# Box-3_Electronics_v6.net
KiCad netlist of a schematic drawn in EAGLE
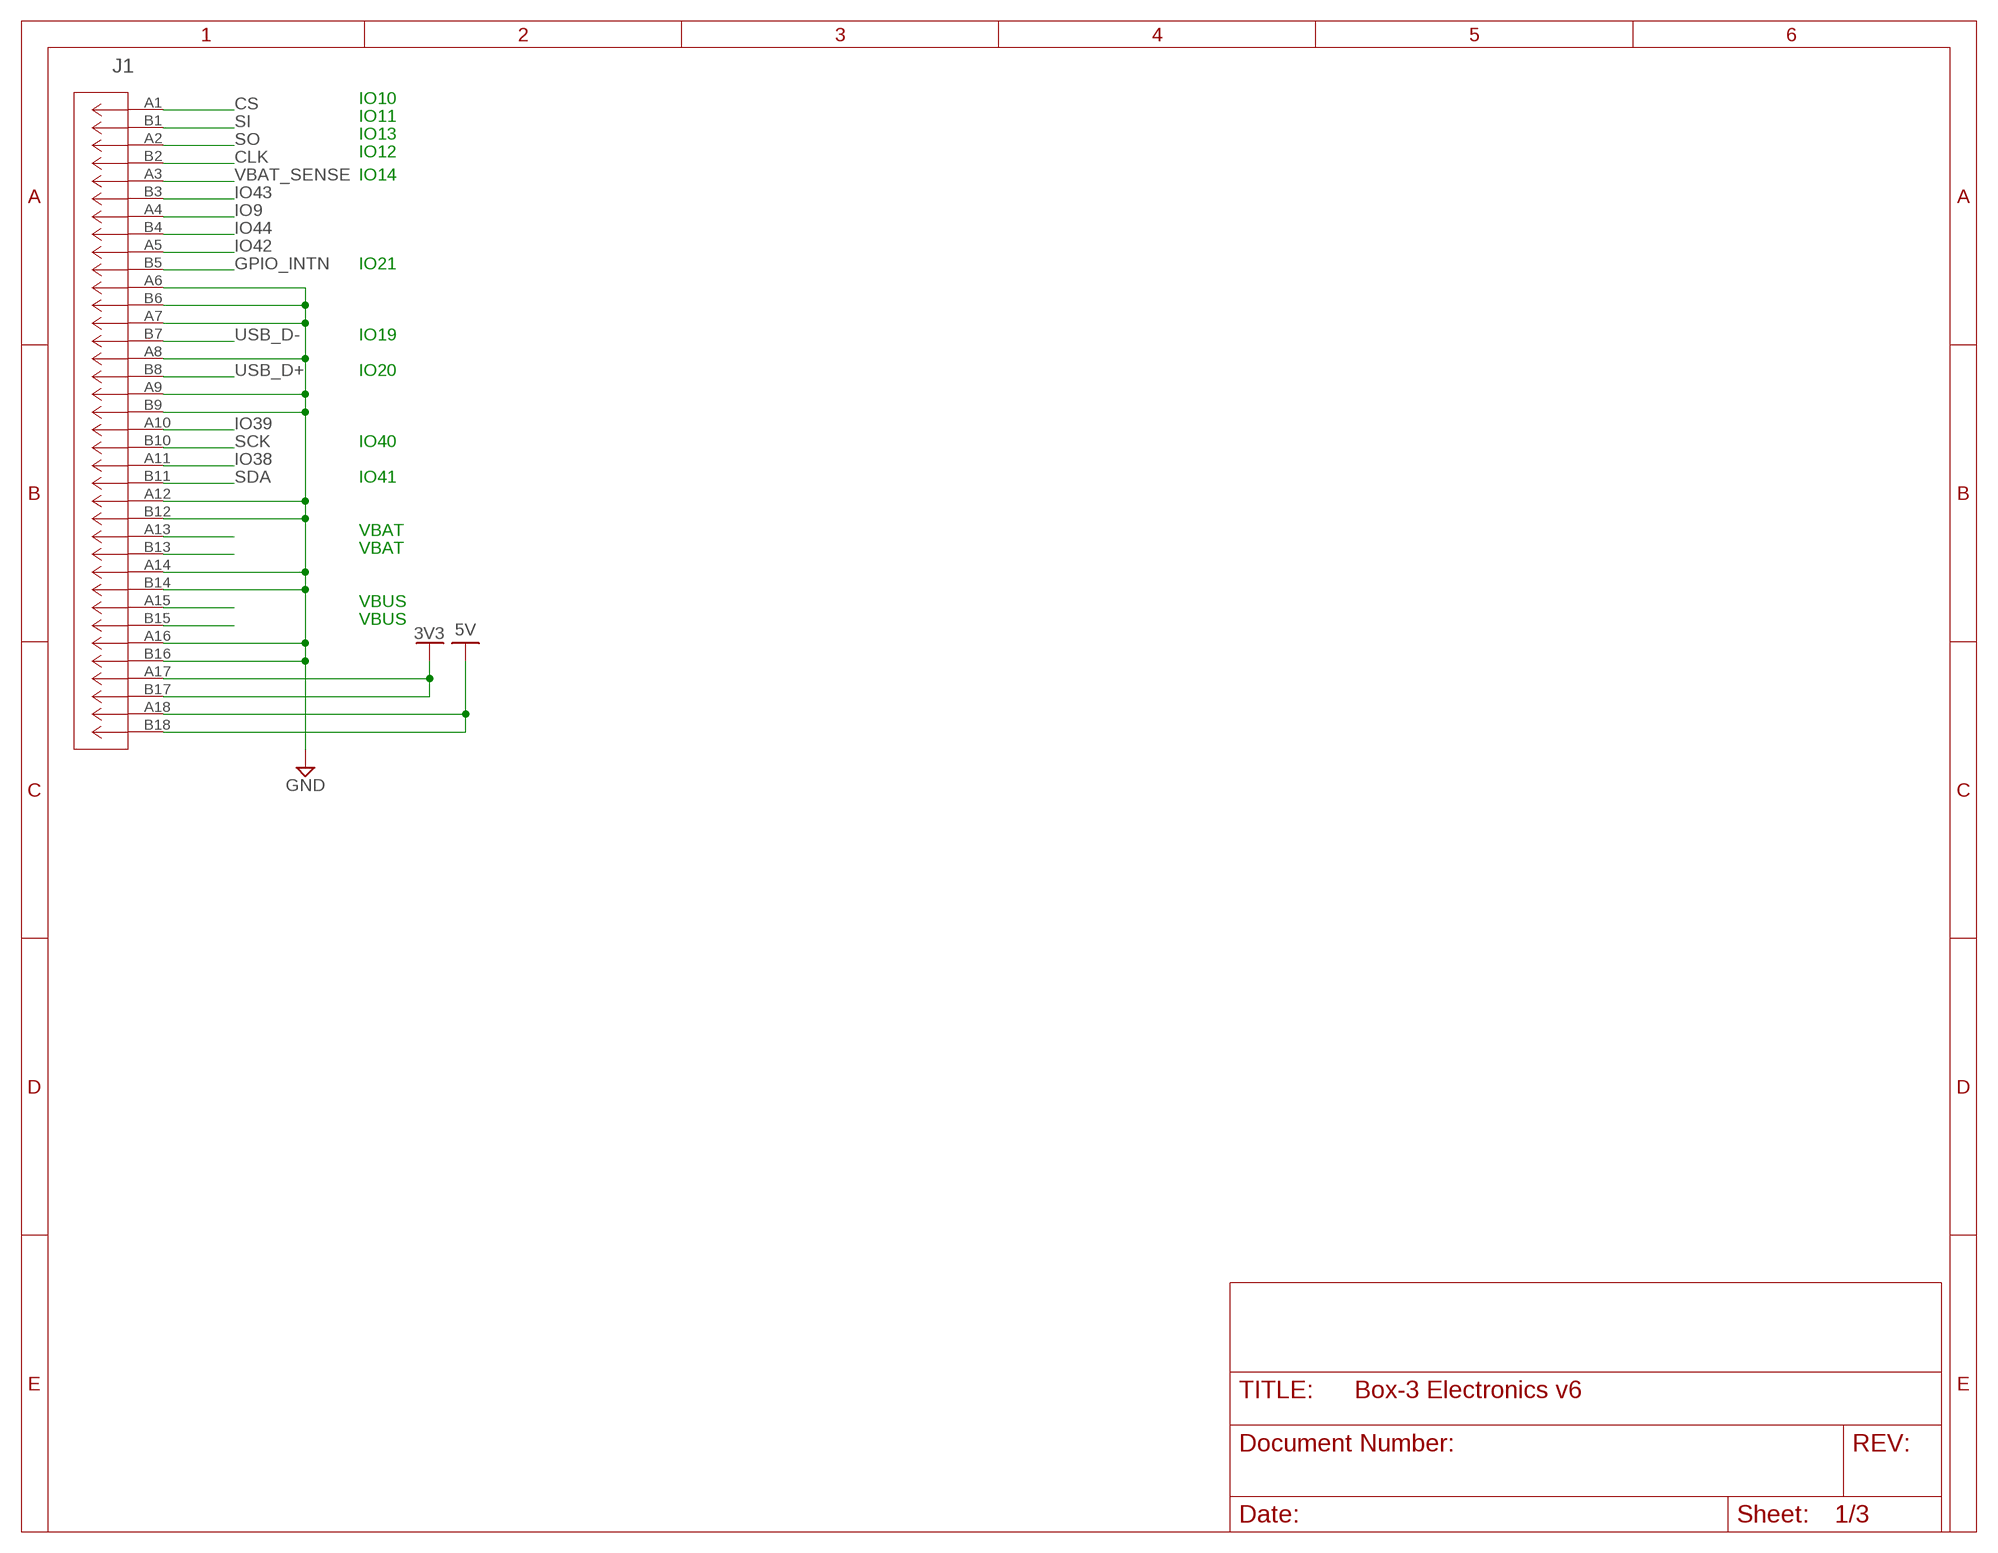
[diagram p0: schematic, sheet 1]
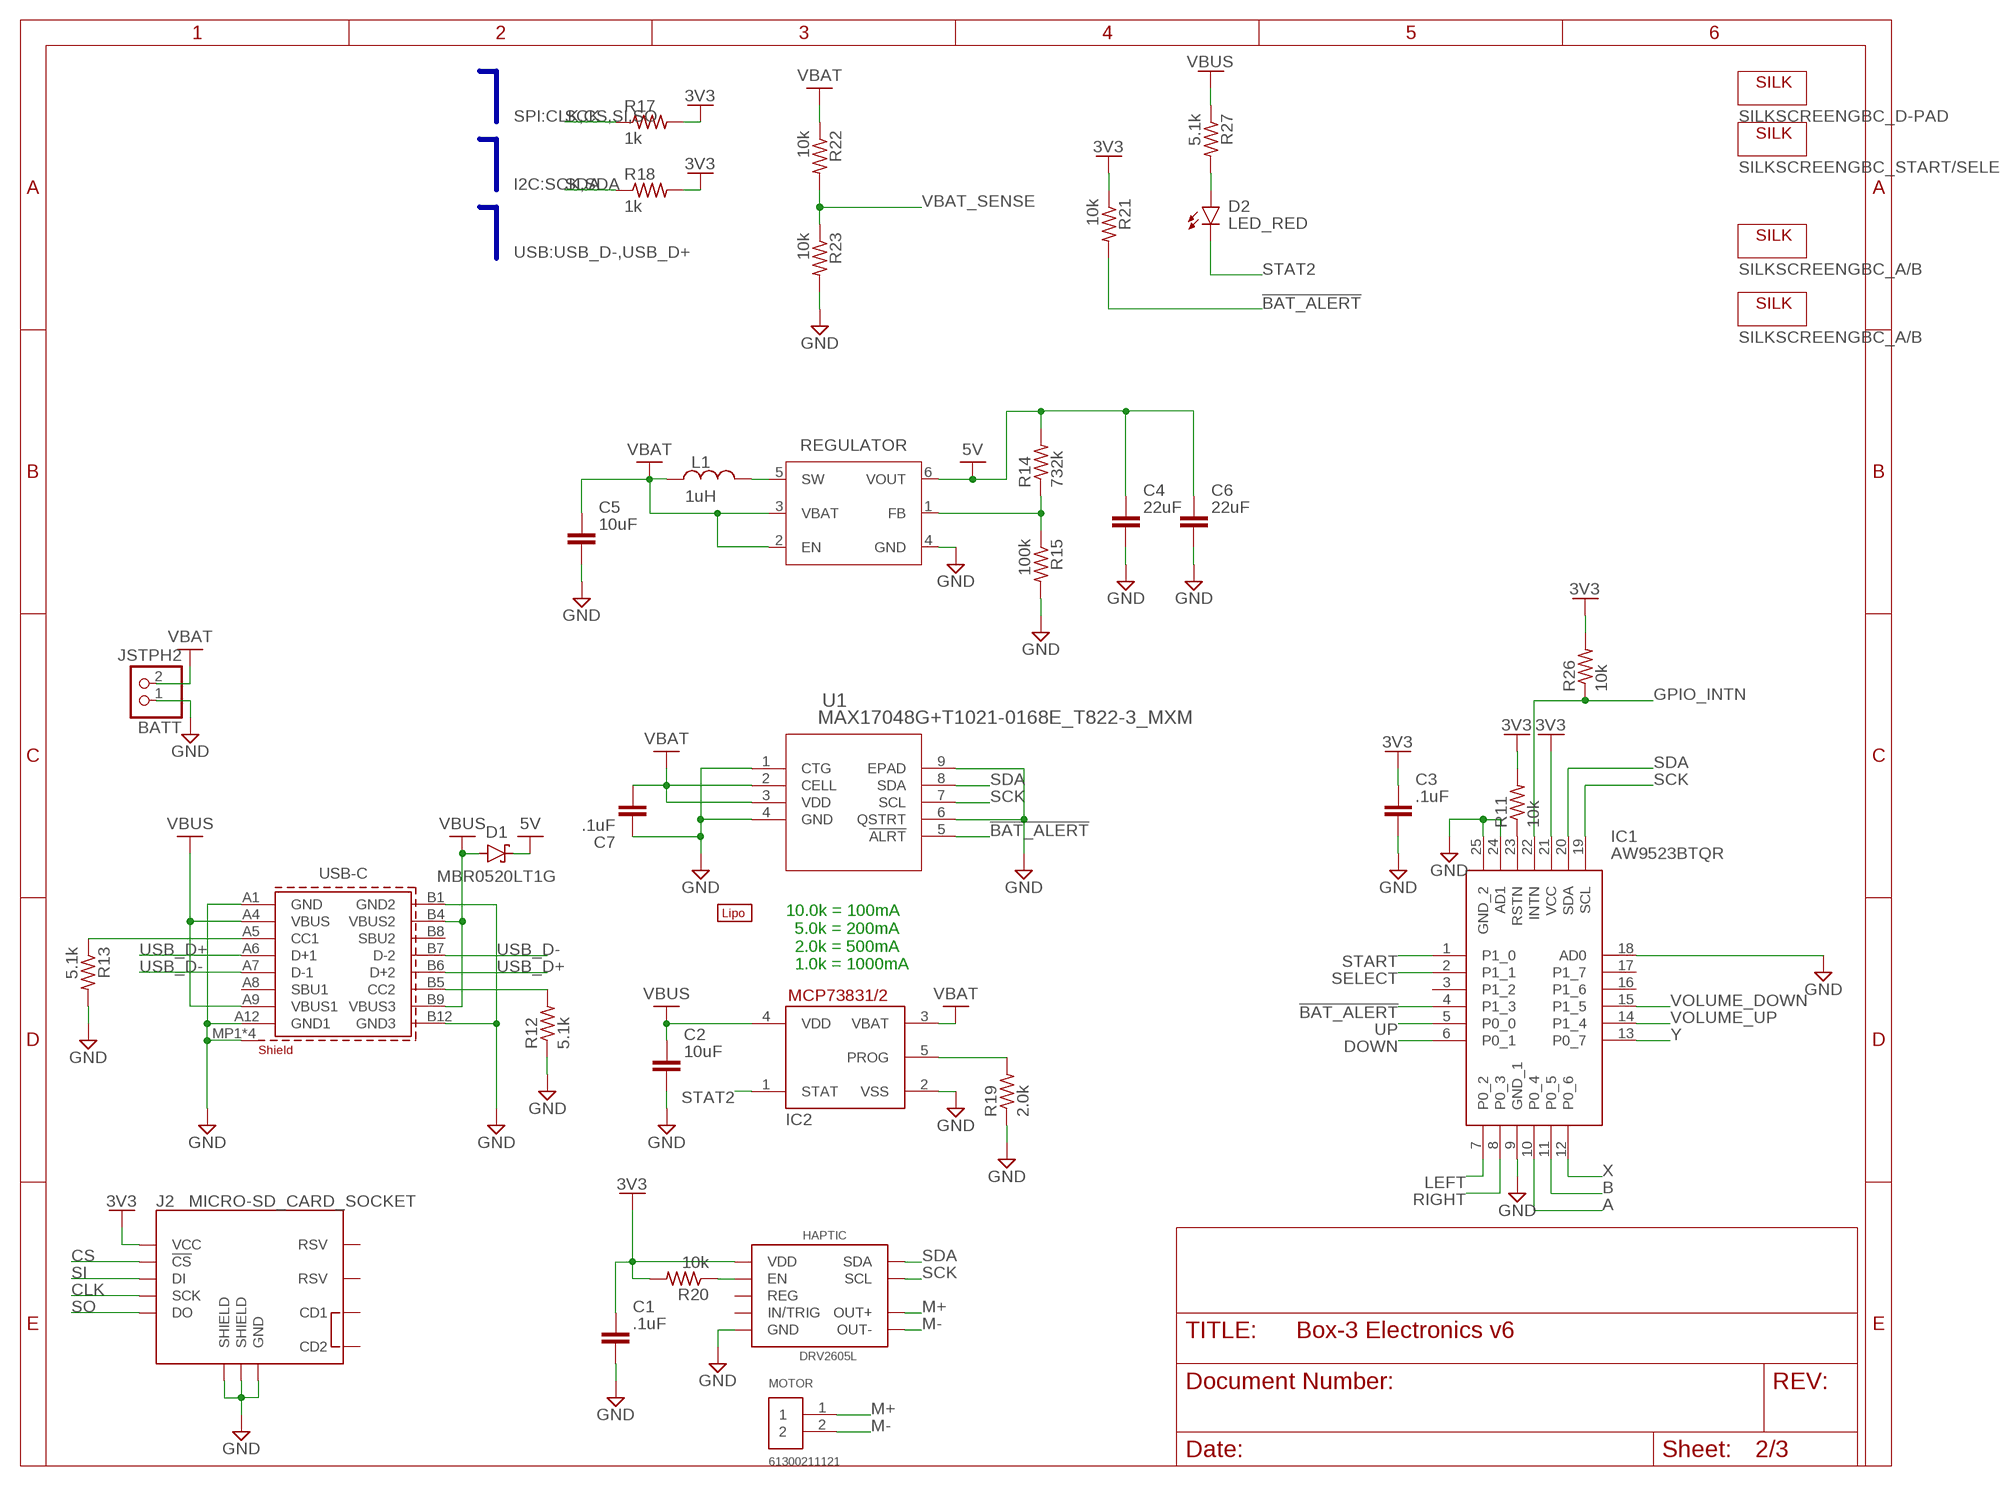
[diagram p1: schematic, sheet 2]
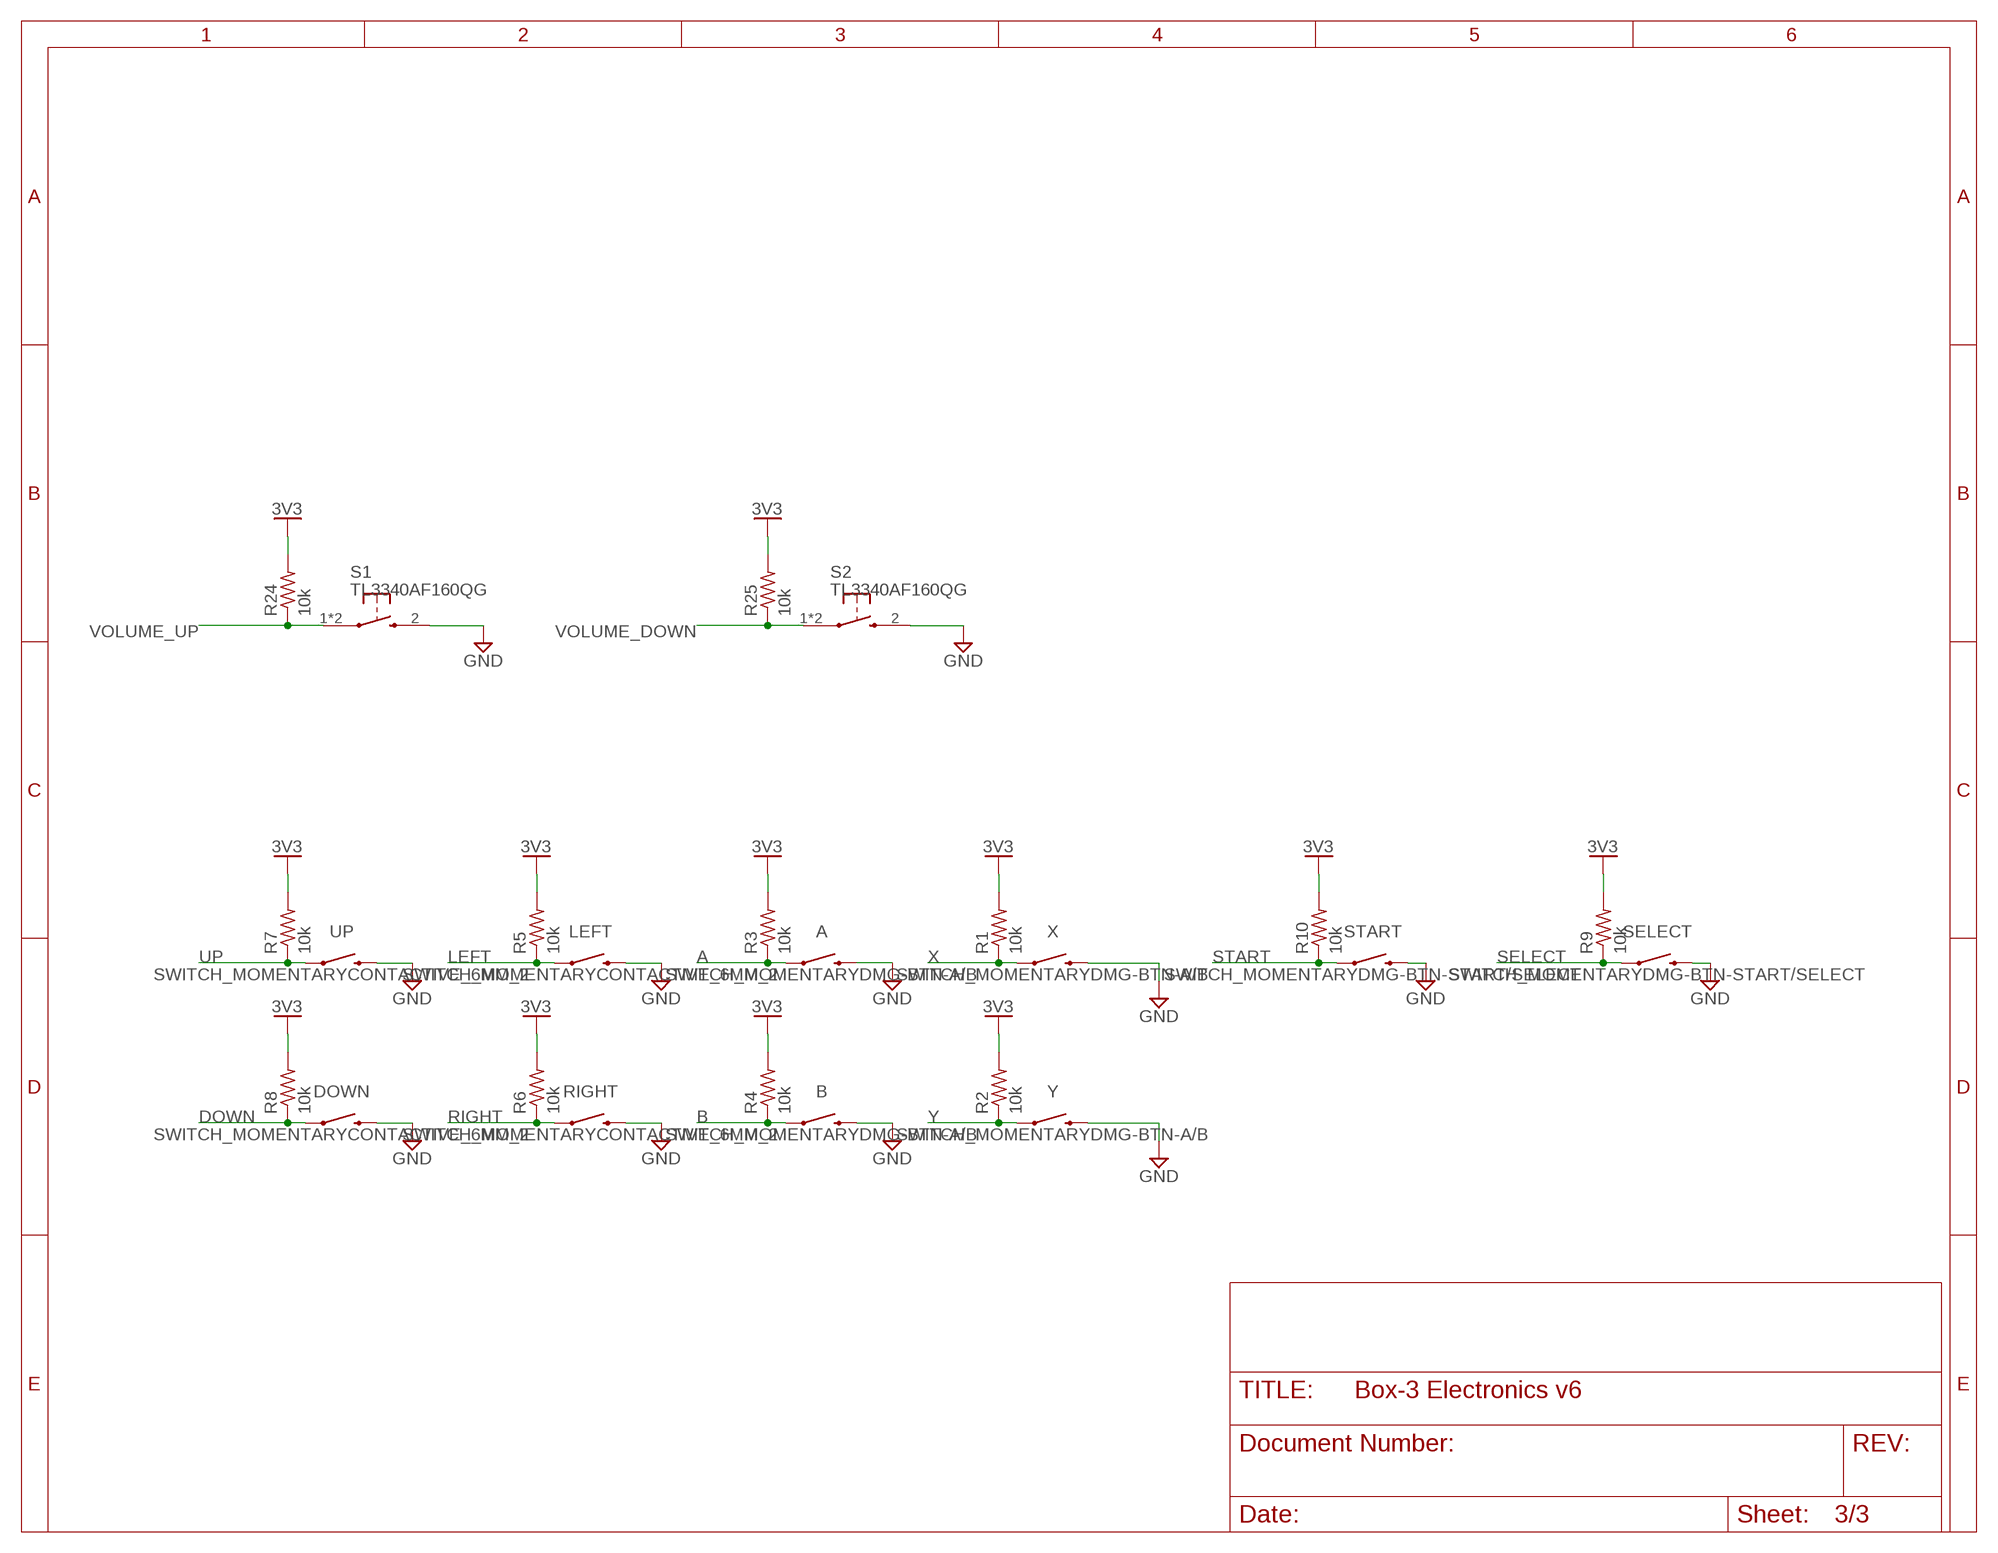
[diagram p2: schematic, sheet 3]

(export (version "E")
  (design (tool "Eeschema 10.0.6"))
  (components
    (comp (ref "A")
      (value "SWITCH_MOMENTARYDMG-BTN-A/B")
      (footprint "eagle-import:DMG_BTN3")
      (libsource (lib "eagle-import") (part "SWITCH_MOMENTARYDMG-BTN-A/B"))
    )
    (comp (ref "B")
      (value "SWITCH_MOMENTARYDMG-BTN-A/B")
      (footprint "eagle-import:DMG_BTN3")
      (libsource (lib "eagle-import") (part "SWITCH_MOMENTARYDMG-BTN-A/B"))
    )
    (comp (ref "DOWN")
      (value "SWITCH_MOMENTARYCONTACTIVE_6MM_2")
      (footprint "eagle-import:BUTTON-CONDUCTIVE_6MM_2")
      (libsource (lib "eagle-import") (part "SWITCH_MOMENTARYCONTACTIVE_6MM_2"))
    )
    (comp (ref "LEFT")
      (value "SWITCH_MOMENTARYCONTACTIVE_6MM_2")
      (footprint "eagle-import:BUTTON-CONDUCTIVE_6MM_2")
      (libsource (lib "eagle-import") (part "SWITCH_MOMENTARYCONTACTIVE_6MM_2"))
    )
    (comp (ref "R1")
      (value "10k")
      (footprint "eagle-import:RESC1608X60")
      (libsource (lib "eagle-import") (part "R-USCHIP-0603(1608-METRIC)_"))
    )
    (comp (ref "R2")
      (value "10k")
      (footprint "eagle-import:RESC1608X60")
      (libsource (lib "eagle-import") (part "R-USCHIP-0603(1608-METRIC)_"))
    )
    (comp (ref "R3")
      (value "10k")
      (footprint "eagle-import:RESC1608X60")
      (libsource (lib "eagle-import") (part "R-USCHIP-0603(1608-METRIC)_"))
    )
    (comp (ref "R4")
      (value "10k")
      (footprint "eagle-import:RESC1608X60")
      (libsource (lib "eagle-import") (part "R-USCHIP-0603(1608-METRIC)_"))
    )
    (comp (ref "R5")
      (value "10k")
      (footprint "eagle-import:RESC1608X60")
      (libsource (lib "eagle-import") (part "R-USCHIP-0603(1608-METRIC)_"))
    )
    (comp (ref "R6")
      (value "10k")
      (footprint "eagle-import:RESC1608X60")
      (libsource (lib "eagle-import") (part "R-USCHIP-0603(1608-METRIC)_"))
    )
    (comp (ref "R7")
      (value "10k")
      (footprint "eagle-import:RESC1608X60")
      (libsource (lib "eagle-import") (part "R-USCHIP-0603(1608-METRIC)_"))
    )
    (comp (ref "R8")
      (value "10k")
      (footprint "eagle-import:RESC1608X60")
      (libsource (lib "eagle-import") (part "R-USCHIP-0603(1608-METRIC)_"))
    )
    (comp (ref "R9")
      (value "10k")
      (footprint "eagle-import:RESC1608X60")
      (libsource (lib "eagle-import") (part "R-USCHIP-0603(1608-METRIC)_"))
    )
    (comp (ref "R10")
      (value "10k")
      (footprint "eagle-import:RESC1608X60")
      (libsource (lib "eagle-import") (part "R-USCHIP-0603(1608-METRIC)_"))
    )
    (comp (ref "R24")
      (value "10k")
      (footprint "eagle-import:RESC1608X60")
      (libsource (lib "eagle-import") (part "R-USCHIP-0603(1608-METRIC)_"))
    )
    (comp (ref "R25")
      (value "10k")
      (footprint "eagle-import:RESC1608X60")
      (libsource (lib "eagle-import") (part "R-USCHIP-0603(1608-METRIC)_"))
    )
    (comp (ref "RIGHT")
      (value "SWITCH_MOMENTARYCONTACTIVE_6MM_2")
      (footprint "eagle-import:BUTTON-CONDUCTIVE_6MM_2")
      (libsource (lib "eagle-import") (part "SWITCH_MOMENTARYCONTACTIVE_6MM_2"))
    )
    (comp (ref "S1")
      (value "TL3340AF160QG")
      (footprint "eagle-import:TL3340")
      (fields (field (name "MOUSER_PART_NUMBER") "612-TL3340AF160QG"))
      (libsource (lib "eagle-import") (part "TL3340AF160QG"))
    )
    (comp (ref "S2")
      (value "TL3340AF160QG")
      (footprint "eagle-import:TL3340")
      (fields (field (name "MOUSER_PART_NUMBER") "612-TL3340AF160QG"))
      (libsource (lib "eagle-import") (part "TL3340AF160QG"))
    )
    (comp (ref "SELECT")
      (value "SWITCH_MOMENTARYDMG-BTN-START/SELECT")
      (footprint "eagle-import:DMG_BTN1_W2")
      (libsource (lib "eagle-import") (part "SWITCH_MOMENTARYDMG-BTN-START/SELECT"))
    )
    (comp (ref "START")
      (value "SWITCH_MOMENTARYDMG-BTN-START/SELECT")
      (footprint "eagle-import:DMG_BTN1_W2")
      (libsource (lib "eagle-import") (part "SWITCH_MOMENTARYDMG-BTN-START/SELECT"))
    )
    (comp (ref "UP")
      (value "SWITCH_MOMENTARYCONTACTIVE_6MM_2")
      (footprint "eagle-import:BUTTON-CONDUCTIVE_6MM_2")
      (libsource (lib "eagle-import") (part "SWITCH_MOMENTARYCONTACTIVE_6MM_2"))
    )
    (comp (ref "X")
      (value "SWITCH_MOMENTARYDMG-BTN-A/B")
      (footprint "eagle-import:DMG_BTN3")
      (libsource (lib "eagle-import") (part "SWITCH_MOMENTARYDMG-BTN-A/B"))
    )
    (comp (ref "Y")
      (value "SWITCH_MOMENTARYDMG-BTN-A/B")
      (footprint "eagle-import:DMG_BTN3")
      (libsource (lib "eagle-import") (part "SWITCH_MOMENTARYDMG-BTN-A/B"))
    )
    (comp (ref "BATT")
      (value "JSTPH2")
      (footprint "eagle-import:JSTPH2")
      (libsource (lib "eagle-import") (part "JSTPH2"))
    )
    (comp (ref "BT1")
      (value "LIPO-OUTLINE1100")
      (footprint "eagle-import:LIPO-1000")
      (libsource (lib "eagle-import") (part "LIPO-OUTLINE1100"))
    )
    (comp (ref "C1")
      (value ".1uF")
      (footprint "eagle-import:CAPC1608X85")
      (libsource (lib "eagle-import") (part "CCHIP-0603(1608-METRIC)_"))
    )
    (comp (ref "C2")
      (value "10uF")
      (footprint "eagle-import:CAPC1608X85")
      (libsource (lib "eagle-import") (part "CCHIP-0603(1608-METRIC)_"))
    )
    (comp (ref "C3")
      (value ".1uF")
      (footprint "eagle-import:CAPC1608X85")
      (libsource (lib "eagle-import") (part "CCHIP-0603(1608-METRIC)_"))
    )
    (comp (ref "C4")
      (value "22uF")
      (footprint "eagle-import:CAPC2012X110")
      (libsource (lib "eagle-import") (part "CCHIP-0805(2012-METRIC)_"))
    )
    (comp (ref "C5")
      (value "10uF")
      (footprint "eagle-import:CAPC1608X85")
      (libsource (lib "eagle-import") (part "CCHIP-0603(1608-METRIC)_"))
    )
    (comp (ref "C6")
      (value "22uF")
      (footprint "eagle-import:CAPC2012X110")
      (libsource (lib "eagle-import") (part "CCHIP-0805(2012-METRIC)_"))
    )
    (comp (ref "C7")
      (value ".1uF")
      (footprint "eagle-import:CAPC1608X85")
      (libsource (lib "eagle-import") (part "CCHIP-0603(1608-METRIC)_"))
    )
    (comp (ref "D1")
      (value "MBR0520LT1G")
      (footprint "eagle-import:SODFL3718X115")
      (fields (field (name "MANUFACTURER") "ON Semiconductor"))
      (libsource (lib "eagle-import") (part "SCHOTTKY_DO-219MBR0520LT1G"))
    )
    (comp (ref "D2")
      (value "LED_RED")
      (footprint "eagle-import:LEDC2012X110N_FLAT-R")
      (fields (field (name "MANUFACTURER") "Wurth Electronik") (field (name "MPN") "150080RS75000"))
      (libsource (lib "eagle-import") (part "CHIP-FLAT-R_0805"))
    )
    (comp (ref "HAPTIC")
      (value "DRV2605L")
      (footprint "eagle-import:VSSOP-10")
      (libsource (lib "eagle-import") (part "DRV2605L"))
    )
    (comp (ref "IC1")
      (value "AW9523BTQR")
      (footprint "eagle-import:QFN50P400X400X80-25N")
      (libsource (lib "eagle-import") (part "AW9523BTQR"))
    )
    (comp (ref "IC2")
      (value "MCP73831/OT")
      (footprint "eagle-import:SOT23-5L")
      (libsource (lib "eagle-import") (part "MCP73831/OT"))
    )
    (comp (ref "J2")
      (value "MICRO-SD_CARD_SOCKET")
      (footprint "eagle-import:MICRO-SD-SOCKET")
      (libsource (lib "eagle-import") (part "MICRO-SD_CARD_SOCKET"))
    )
    (comp (ref "L1")
      (value "1uH")
      (footprint "eagle-import:INDC2009X120")
      (libsource (lib "eagle-import") (part "LCHIP-0805(2012-METRIC)_"))
    )
    (comp (ref "MOTOR")
      (value "61300211121")
      (footprint "eagle-import:61300211121")
      (fields
        (field (name "DIGI_KEY_PART_NUMBER") "732-5315-ND")
        (field (name "MANUFACTURER") "Wurth Electronics Inc.")
        (field (name "CREATED_BY") "PCBLayout.com")
      )
      (libsource (lib "eagle-import") (part "61300211121"))
    )
    (comp (ref "R11")
      (value "10k")
      (footprint "eagle-import:RESC1608X60")
      (libsource (lib "eagle-import") (part "R-USCHIP-0603(1608-METRIC)_"))
    )
    (comp (ref "R12")
      (value "5.1k")
      (footprint "eagle-import:RESC1608X60")
      (libsource (lib "eagle-import") (part "R-USCHIP-0603(1608-METRIC)_"))
    )
    (comp (ref "R13")
      (value "5.1k")
      (footprint "eagle-import:RESC1608X60")
      (libsource (lib "eagle-import") (part "R-USCHIP-0603(1608-METRIC)_"))
    )
    (comp (ref "R14")
      (value "732k")
      (footprint "eagle-import:RESC1608X60")
      (libsource (lib "eagle-import") (part "R-USCHIP-0603(1608-METRIC)_"))
    )
    (comp (ref "R15")
      (value "100k")
      (footprint "eagle-import:RESC1608X60")
      (libsource (lib "eagle-import") (part "R-USCHIP-0603(1608-METRIC)_"))
    )
    (comp (ref "R17")
      (value "1k")
      (footprint "eagle-import:RESC1608X60")
      (libsource (lib "eagle-import") (part "R-USCHIP-0603(1608-METRIC)_"))
    )
    (comp (ref "R18")
      (value "1k")
      (footprint "eagle-import:RESC1608X60")
      (libsource (lib "eagle-import") (part "R-USCHIP-0603(1608-METRIC)_"))
    )
    (comp (ref "R19")
      (value "2.0k")
      (footprint "eagle-import:RESC1608X60")
      (libsource (lib "eagle-import") (part "R-USCHIP-0603(1608-METRIC)_"))
    )
    (comp (ref "R20")
      (value "10k")
      (footprint "eagle-import:RESC1608X60")
      (libsource (lib "eagle-import") (part "R-USCHIP-0603(1608-METRIC)_"))
    )
    (comp (ref "R21")
      (value "10k")
      (footprint "eagle-import:RESC1608X60")
      (libsource (lib "eagle-import") (part "R-USCHIP-0603(1608-METRIC)_"))
    )
    (comp (ref "R22")
      (value "10k")
      (footprint "eagle-import:RESC1608X60")
      (libsource (lib "eagle-import") (part "R-USCHIP-0603(1608-METRIC)_"))
    )
    (comp (ref "R23")
      (value "10k")
      (footprint "eagle-import:RESC1608X60")
      (libsource (lib "eagle-import") (part "R-USCHIP-0603(1608-METRIC)_"))
    )
    (comp (ref "R26")
      (value "10k")
      (footprint "eagle-import:RESC1608X60")
      (libsource (lib "eagle-import") (part "R-USCHIP-0603(1608-METRIC)_"))
    )
    (comp (ref "R27")
      (value "5.1k")
      (footprint "eagle-import:RESC1608X60")
      (libsource (lib "eagle-import") (part "R-USCHIP-0603(1608-METRIC)_"))
    )
    (comp (ref "REGULATOR")
      (value "TPS61070")
      (footprint "eagle-import:SOT563")
      (libsource (lib "eagle-import") (part "TPS61023"))
    )
    (comp (ref "U$1")
      (value "SILKSCREENGBC_D-PAD")
      (footprint "eagle-import:GAMEBOY_COLOR_DPAD_SILK")
      (libsource (lib "eagle-import") (part "SILKSCREENGBC_D-PAD"))
    )
    (comp (ref "U$2")
      (value "SILKSCREENGBC_START/SELECT")
      (footprint "eagle-import:GAMEBOY_COLOR_START_SELECT_SILK")
      (libsource (lib "eagle-import") (part "SILKSCREENGBC_START/SELECT"))
    )
    (comp (ref "U$3")
      (value "SILKSCREENGBC_A/B")
      (footprint "eagle-import:GAMEBOY_COLOR_A_B_BUTTON_MEMBRANE")
      (libsource (lib "eagle-import") (part "SILKSCREENGBC_A/B"))
    )
    (comp (ref "U$4")
      (value "SILKSCREENGBC_A/B")
      (footprint "eagle-import:GAMEBOY_COLOR_A_B_BUTTON_MEMBRANE")
      (libsource (lib "eagle-import") (part "SILKSCREENGBC_A/B"))
    )
    (comp (ref "U1")
      (value "MAX17048G+T1021-0168E_T822-3_MXM")
      (footprint "eagle-import:21-0168E_T822-3_MXM")
      (fields
        (field (name "MANUFACTURER_PART_NUMBER") "MAX17048G+T10")
        (field (name "COPYRIGHT") "Copyright (C) 2023 Ultra Librarian. All rights reserved.")
      )
      (libsource (lib "eagle-import") (part "MAX17048G+T1021-0168E_T822-3_MXM"))
    )
    (comp (ref "USB-C")
      (value "629722000214")
      (footprint "eagle-import:USB4110GFA")
      (libsource (lib "eagle-import") (part "629722000214SMD"))
    )
    (comp (ref "J1")
      (value "5-1734857-1CONN_5-1734857-1_TEC")
      (footprint "eagle-import:CONN_5-1734857-1_TEC")
      (fields
        (field (name "MANUFACTURER_PART_NUMBER") "5-1734857-1")
        (field (name "COPYRIGHT") "Copyright (C) 2023 Ultra Librarian. All rights reserved.")
      )
      (libsource (lib "eagle-import") (part "5-1734857-1CONN_5-1734857-1_TEC"))
    )
  )
  (nets
    (net (code "7") (name "3V3") (class "Default")
      (node (ref "C1") (pin "1") (pinfunction "1_1") (pintype "passive"))
      (node (ref "C3") (pin "1") (pinfunction "1_1") (pintype "passive"))
      (node (ref "HAPTIC") (pin "10") (pinfunction "VDD_10") (pintype "bidirectional"))
      (node (ref "HAPTIC") (pin "6") (pinfunction "VDD_6") (pintype "bidirectional"))
      (node (ref "IC1") (pin "21") (pinfunction "VCC_21") (pintype "bidirectional"))
      (node (ref "J1") (pin "A17") (pinfunction "A17_A17") (pintype "passive"))
      (node (ref "J1") (pin "B17") (pinfunction "B17_B17") (pintype "passive"))
      (node (ref "J2") (pin "VCC") (pinfunction "VCC_VCC") (pintype "bidirectional"))
      (node (ref "R1") (pin "2") (pinfunction "2_2") (pintype "passive"))
      (node (ref "R10") (pin "2") (pinfunction "2_2") (pintype "passive"))
      (node (ref "R11") (pin "2") (pinfunction "2_2") (pintype "passive"))
      (node (ref "R17") (pin "2") (pinfunction "2_2") (pintype "passive"))
      (node (ref "R18") (pin "2") (pinfunction "2_2") (pintype "passive"))
      (node (ref "R2") (pin "2") (pinfunction "2_2") (pintype "passive"))
      (node (ref "R20") (pin "2") (pinfunction "2_2") (pintype "passive"))
      (node (ref "R21") (pin "1") (pinfunction "1_1") (pintype "passive"))
      (node (ref "R24") (pin "2") (pinfunction "2_2") (pintype "passive"))
      (node (ref "R25") (pin "2") (pinfunction "2_2") (pintype "passive"))
      (node (ref "R26") (pin "2") (pinfunction "2_2") (pintype "passive"))
      (node (ref "R3") (pin "2") (pinfunction "2_2") (pintype "passive"))
      (node (ref "R4") (pin "2") (pinfunction "2_2") (pintype "passive"))
      (node (ref "R5") (pin "2") (pinfunction "2_2") (pintype "passive"))
      (node (ref "R6") (pin "2") (pinfunction "2_2") (pintype "passive"))
      (node (ref "R7") (pin "2") (pinfunction "2_2") (pintype "passive"))
      (node (ref "R8") (pin "2") (pinfunction "2_2") (pintype "passive"))
      (node (ref "R9") (pin "2") (pinfunction "2_2") (pintype "passive"))
    )
    (net (code "8") (name "5V") (class "Default")
      (node (ref "C4") (pin "1") (pinfunction "1_1") (pintype "passive"))
      (node (ref "C6") (pin "1") (pinfunction "1_1") (pintype "passive"))
      (node (ref "D1") (pin "1") (pinfunction "C_1") (pintype "passive"))
      (node (ref "J1") (pin "A18") (pinfunction "A18_A18") (pintype "passive"))
      (node (ref "J1") (pin "B18") (pinfunction "B18_B18") (pintype "passive"))
      (node (ref "R14") (pin "2") (pinfunction "2_2") (pintype "passive"))
      (node (ref "REGULATOR") (pin "6") (pinfunction "VOUT_6") (pintype "output"))
    )
    (net (code "9") (name "A") (class "Default")
      (node (ref "A") (pin "P$1") (pinfunction "1_P$1") (pintype "passive"))
      (node (ref "A") (pin "P$3") (pinfunction "1_P$3") (pintype "passive"))
      (node (ref "IC1") (pin "10") (pinfunction "P0_4_10") (pintype "bidirectional"))
      (node (ref "R3") (pin "1") (pinfunction "1_1") (pintype "passive"))
    )
    (net (code "10") (name "B") (class "Default")
      (node (ref "B") (pin "P$1") (pinfunction "1_P$1") (pintype "passive"))
      (node (ref "B") (pin "P$3") (pinfunction "1_P$3") (pintype "passive"))
      (node (ref "IC1") (pin "11") (pinfunction "P0_5_11") (pintype "bidirectional"))
      (node (ref "R4") (pin "1") (pinfunction "1_1") (pintype "passive"))
    )
    (net (code "11") (name "CLK") (class "Default")
      (node (ref "J1") (pin "B2") (pinfunction "B2_B2") (pintype "passive"))
      (node (ref "J2") (pin "SCLK") (pinfunction "SCK_SCLK") (pintype "bidirectional"))
    )
    (net (code "12") (name "CS") (class "Default")
      (node (ref "J1") (pin "A1") (pinfunction "A1_A1") (pintype "passive"))
      (node (ref "J2") (pin "CS") (pinfunction "~{CS}_CS") (pintype "bidirectional"))
    )
    (net (code "13") (name "DOWN") (class "Default")
      (node (ref "DOWN") (pin "1") (pinfunction "1_1") (pintype "passive"))
      (node (ref "IC1") (pin "6") (pinfunction "P0_1_6") (pintype "bidirectional"))
      (node (ref "R8") (pin "1") (pinfunction "1_1") (pintype "passive"))
    )
    (net (code "14") (name "GND") (class "Default")
      (node (ref "A") (pin "P$2") (pinfunction "2_P$2") (pintype "passive"))
      (node (ref "A") (pin "P$4") (pinfunction "2_P$4") (pintype "passive"))
      (node (ref "B") (pin "P$2") (pinfunction "2_P$2") (pintype "passive"))
      (node (ref "B") (pin "P$4") (pinfunction "2_P$4") (pintype "passive"))
      (node (ref "BATT") (pin "1") (pinfunction "1_1") (pintype "passive"))
      (node (ref "C1") (pin "2") (pinfunction "2_2") (pintype "passive"))
      (node (ref "C2") (pin "2") (pinfunction "2_2") (pintype "passive"))
      (node (ref "C3") (pin "2") (pinfunction "2_2") (pintype "passive"))
      (node (ref "C4") (pin "2") (pinfunction "2_2") (pintype "passive"))
      (node (ref "C5") (pin "2") (pinfunction "2_2") (pintype "passive"))
      (node (ref "C6") (pin "2") (pinfunction "2_2") (pintype "passive"))
      (node (ref "C7") (pin "1") (pinfunction "1_1") (pintype "passive"))
      (node (ref "DOWN") (pin "2") (pinfunction "2_2") (pintype "passive"))
      (node (ref "HAPTIC") (pin "8") (pinfunction "GND_8") (pintype "bidirectional"))
      (node (ref "IC1") (pin "18") (pinfunction "AD0_18") (pintype "bidirectional"))
      (node (ref "IC1") (pin "24") (pinfunction "AD1_24") (pintype "bidirectional"))
      (node (ref "IC1") (pin "25") (pinfunction "GND_2_25") (pintype "bidirectional"))
      (node (ref "IC1") (pin "9") (pinfunction "GND_1_9") (pintype "bidirectional"))
      (node (ref "IC2") (pin "2") (pinfunction "VSS_2") (pintype "power_in"))
      (node (ref "J1") (pin "A12") (pinfunction "A12_A12") (pintype "passive"))
      (node (ref "J1") (pin "A14") (pinfunction "A14_A14") (pintype "passive"))
      (node (ref "J1") (pin "A16") (pinfunction "A16_A16") (pintype "passive"))
      (node (ref "J1") (pin "A6") (pinfunction "A6_A6") (pintype "passive"))
      (node (ref "J1") (pin "A7") (pinfunction "A7_A7") (pintype "passive"))
      (node (ref "J1") (pin "A8") (pinfunction "A8_A8") (pintype "passive"))
      (node (ref "J1") (pin "A9") (pinfunction "A9_A9") (pintype "passive"))
      (node (ref "J1") (pin "B12") (pinfunction "B12_B12") (pintype "passive"))
      (node (ref "J1") (pin "B14") (pinfunction "B14_B14") (pintype "passive"))
      (node (ref "J1") (pin "B16") (pinfunction "B16_B16") (pintype "passive"))
      (node (ref "J1") (pin "B6") (pinfunction "B6_B6") (pintype "passive"))
      (node (ref "J1") (pin "B9") (pinfunction "B9_B9") (pintype "passive"))
      (node (ref "J2") (pin "GND") (pinfunction "GND_GND") (pintype "bidirectional"))
      (node (ref "J2") (pin "GND1") (pinfunction "SHIELD_GND1") (pintype "bidirectional"))
      (node (ref "J2") (pin "GND3") (pinfunction "SHIELD_GND3") (pintype "bidirectional"))
      (node (ref "LEFT") (pin "2") (pinfunction "2_2") (pintype "passive"))
      (node (ref "R12") (pin "1") (pinfunction "1_1") (pintype "passive"))
      (node (ref "R13") (pin "2") (pinfunction "2_2") (pintype "passive"))
      (node (ref "R15") (pin "2") (pinfunction "2_2") (pintype "passive"))
      (node (ref "R19") (pin "1") (pinfunction "1_1") (pintype "passive"))
      (node (ref "R23") (pin "2") (pinfunction "2_2") (pintype "passive"))
      (node (ref "REGULATOR") (pin "4") (pinfunction "GND_4") (pintype "power_in"))
      (node (ref "RIGHT") (pin "2") (pinfunction "2_2") (pintype "passive"))
      (node (ref "S1") (pin "2") (pinfunction "2_2") (pintype "bidirectional"))
      (node (ref "S2") (pin "2") (pinfunction "2_2") (pintype "bidirectional"))
      (node (ref "SELECT") (pin "P$2") (pinfunction "2_P$2") (pintype "passive"))
      (node (ref "SELECT") (pin "P$4") (pinfunction "2_P$4") (pintype "passive"))
      (node (ref "START") (pin "P$2") (pinfunction "2_P$2") (pintype "passive"))
      (node (ref "START") (pin "P$4") (pinfunction "2_P$4") (pintype "passive"))
      (node (ref "U1") (pin "1") (pinfunction "CTG_1") (pintype "passive"))
      (node (ref "U1") (pin "4") (pinfunction "GND_4") (pintype "power_in"))
      (node (ref "U1") (pin "6") (pinfunction "QSTRT_6") (pintype "input"))
      (node (ref "U1") (pin "9") (pinfunction "EPAD_9") (pintype "passive"))
      (node (ref "UP") (pin "2") (pinfunction "2_2") (pintype "passive"))
      (node (ref "USB-C") (pin "A1") (pinfunction "GND_A1") (pintype "passive"))
      (node (ref "USB-C") (pin "A12") (pinfunction "GND1_A12") (pintype "passive"))
      (node (ref "USB-C") (pin "B1") (pinfunction "GND2_B1") (pintype "passive"))
      (node (ref "USB-C") (pin "B12") (pinfunction "GND3_B12") (pintype "passive"))
      (node (ref "USB-C") (pin "MP1") (pinfunction "SHIELD_MP1") (pintype "passive"))
      (node (ref "USB-C") (pin "MP2") (pinfunction "SHIELD_MP2") (pintype "passive"))
      (node (ref "USB-C") (pin "MP3") (pinfunction "SHIELD_MP3") (pintype "passive"))
      (node (ref "USB-C") (pin "MP4") (pinfunction "SHIELD_MP4") (pintype "passive"))
      (node (ref "X") (pin "P$2") (pinfunction "2_P$2") (pintype "passive"))
      (node (ref "X") (pin "P$4") (pinfunction "2_P$4") (pintype "passive"))
      (node (ref "Y") (pin "P$2") (pinfunction "2_P$2") (pintype "passive"))
      (node (ref "Y") (pin "P$4") (pinfunction "2_P$4") (pintype "passive"))
    )
    (net (code "15") (name "GPIO_INTN") (class "Default")
      (node (ref "IC1") (pin "22") (pinfunction "INTN_22") (pintype "bidirectional"))
      (node (ref "J1") (pin "B5") (pinfunction "B5_B5") (pintype "passive"))
      (node (ref "R26") (pin "1") (pinfunction "1_1") (pintype "passive"))
    )
    (net (code "16") (name "IO9") (class "Default")
      (node (ref "J1") (pin "A4") (pinfunction "A4_A4") (pintype "passive"))
    )
    (net (code "17") (name "IO38") (class "Default")
      (node (ref "J1") (pin "A11") (pinfunction "A11_A11") (pintype "passive"))
    )
    (net (code "18") (name "IO39") (class "Default")
      (node (ref "J1") (pin "A10") (pinfunction "A10_A10") (pintype "passive"))
    )
    (net (code "19") (name "IO42") (class "Default")
      (node (ref "J1") (pin "A5") (pinfunction "A5_A5") (pintype "passive"))
    )
    (net (code "20") (name "IO43") (class "Default")
      (node (ref "J1") (pin "B3") (pinfunction "B3_B3") (pintype "passive"))
    )
    (net (code "21") (name "IO44") (class "Default")
      (node (ref "J1") (pin "B4") (pinfunction "B4_B4") (pintype "passive"))
    )
    (net (code "22") (name "LEFT") (class "Default")
      (node (ref "IC1") (pin "7") (pinfunction "P0_2_7") (pintype "bidirectional"))
      (node (ref "LEFT") (pin "1") (pinfunction "1_1") (pintype "passive"))
      (node (ref "R5") (pin "1") (pinfunction "1_1") (pintype "passive"))
    )
    (net (code "23") (name "M+") (class "Default")
      (node (ref "HAPTIC") (pin "7") (pinfunction "OUT+_7") (pintype "bidirectional"))
      (node (ref "MOTOR") (pin "1") (pinfunction "1_1") (pintype "passive"))
    )
    (net (code "24") (name "M-") (class "Default")
      (node (ref "HAPTIC") (pin "9") (pinfunction "OUT-_9") (pintype "bidirectional"))
      (node (ref "MOTOR") (pin "2") (pinfunction "2_2") (pintype "passive"))
    )
    (net (code "25") (name "Net-(D2-PadA)") (class "Default")
      (node (ref "D2") (pin "A") (pinfunction "A_A") (pintype "passive"))
      (node (ref "R27") (pin "2") (pinfunction "2_2") (pintype "passive"))
    )
    (net (code "26") (name "Net-(HAPTIC-EN)") (class "Default")
      (node (ref "HAPTIC") (pin "5") (pinfunction "EN_5") (pintype "bidirectional"))
      (node (ref "R20") (pin "1") (pinfunction "1_1") (pintype "passive"))
    )
    (net (code "27") (name "Net-(IC1-RSTN)") (class "Default")
      (node (ref "IC1") (pin "23") (pinfunction "RSTN_23") (pintype "bidirectional"))
      (node (ref "R11") (pin "1") (pinfunction "1_1") (pintype "passive"))
    )
    (net (code "28") (name "Net-(IC2-PROG)") (class "Default")
      (node (ref "IC2") (pin "5") (pinfunction "PROG_5") (pintype "input"))
      (node (ref "R19") (pin "2") (pinfunction "2_2") (pintype "passive"))
    )
    (net (code "29") (name "Net-(REGULATOR-FB)") (class "Default")
      (node (ref "R14") (pin "1") (pinfunction "1_1") (pintype "passive"))
      (node (ref "R15") (pin "1") (pinfunction "1_1") (pintype "passive"))
      (node (ref "REGULATOR") (pin "1") (pinfunction "FB_1") (pintype "input"))
    )
    (net (code "30") (name "Net-(REGULATOR-SW)") (class "Default")
      (node (ref "L1") (pin "2") (pinfunction "2_2") (pintype "passive"))
      (node (ref "REGULATOR") (pin "5") (pinfunction "SW_5") (pintype "input"))
    )
    (net (code "31") (name "Net-(USB-C-CC1)") (class "Default")
      (node (ref "R13") (pin "1") (pinfunction "1_1") (pintype "passive"))
      (node (ref "USB-C") (pin "A5") (pinfunction "CC1_A5") (pintype "passive"))
    )
    (net (code "32") (name "Net-(USB-C-CC2)") (class "Default")
      (node (ref "R12") (pin "2") (pinfunction "2_2") (pintype "passive"))
      (node (ref "USB-C") (pin "B5") (pinfunction "CC2_B5") (pintype "passive"))
    )
    (net (code "33") (name "RIGHT") (class "Default")
      (node (ref "IC1") (pin "8") (pinfunction "P0_3_8") (pintype "bidirectional"))
      (node (ref "R6") (pin "1") (pinfunction "1_1") (pintype "passive"))
      (node (ref "RIGHT") (pin "1") (pinfunction "1_1") (pintype "passive"))
    )
    (net (code "34") (name "SCK") (class "Default")
      (node (ref "HAPTIC") (pin "2") (pinfunction "SCL_2") (pintype "bidirectional"))
      (node (ref "IC1") (pin "19") (pinfunction "SCL_19") (pintype "bidirectional"))
      (node (ref "J1") (pin "B10") (pinfunction "B10_B10") (pintype "passive"))
      (node (ref "R17") (pin "1") (pinfunction "1_1") (pintype "passive"))
      (node (ref "U1") (pin "7") (pinfunction "SCL_7") (pintype "input"))
    )
    (net (code "35") (name "SDA") (class "Default")
      (node (ref "HAPTIC") (pin "3") (pinfunction "SDA_3") (pintype "bidirectional"))
      (node (ref "IC1") (pin "20") (pinfunction "SDA_20") (pintype "bidirectional"))
      (node (ref "J1") (pin "B11") (pinfunction "B11_B11") (pintype "passive"))
      (node (ref "R18") (pin "1") (pinfunction "1_1") (pintype "passive"))
      (node (ref "U1") (pin "8") (pinfunction "SDA_8") (pintype "bidirectional"))
    )
    (net (code "36") (name "SELECT") (class "Default")
      (node (ref "IC1") (pin "2") (pinfunction "P1_1_2") (pintype "bidirectional"))
      (node (ref "R9") (pin "1") (pinfunction "1_1") (pintype "passive"))
      (node (ref "SELECT") (pin "P$1") (pinfunction "1_P$1") (pintype "passive"))
      (node (ref "SELECT") (pin "P$3") (pinfunction "1_P$3") (pintype "passive"))
    )
    (net (code "37") (name "SI") (class "Default")
      (node (ref "J1") (pin "B1") (pinfunction "B1_B1") (pintype "passive"))
      (node (ref "J2") (pin "DI") (pinfunction "DI_DI") (pintype "bidirectional"))
    )
    (net (code "38") (name "SO") (class "Default")
      (node (ref "J1") (pin "A2") (pinfunction "A2_A2") (pintype "passive"))
      (node (ref "J2") (pin "DO") (pinfunction "DO_DO") (pintype "bidirectional"))
    )
    (net (code "39") (name "START") (class "Default")
      (node (ref "IC1") (pin "1") (pinfunction "P1_0_1") (pintype "bidirectional"))
      (node (ref "R10") (pin "1") (pinfunction "1_1") (pintype "passive"))
      (node (ref "START") (pin "P$1") (pinfunction "1_P$1") (pintype "passive"))
      (node (ref "START") (pin "P$3") (pinfunction "1_P$3") (pintype "passive"))
    )
    (net (code "40") (name "STAT2") (class "Default")
      (node (ref "D2") (pin "C") (pinfunction "C_C") (pintype "passive"))
      (node (ref "IC2") (pin "1") (pinfunction "STAT_1") (pintype "output"))
    )
    (net (code "41") (name "UP") (class "Default")
      (node (ref "IC1") (pin "5") (pinfunction "P0_0_5") (pintype "bidirectional"))
      (node (ref "R7") (pin "1") (pinfunction "1_1") (pintype "passive"))
      (node (ref "UP") (pin "1") (pinfunction "1_1") (pintype "passive"))
    )
    (net (code "42") (name "USB_D+") (class "Default")
      (node (ref "J1") (pin "B8") (pinfunction "B8_B8") (pintype "passive"))
      (node (ref "USB-C") (pin "A6") (pinfunction "D+1_A6") (pintype "passive"))
      (node (ref "USB-C") (pin "B6") (pinfunction "D+2_B6") (pintype "passive"))
    )
    (net (code "43") (name "USB_D-") (class "Default")
      (node (ref "J1") (pin "B7") (pinfunction "B7_B7") (pintype "passive"))
      (node (ref "USB-C") (pin "A7") (pinfunction "D-1_A7") (pintype "passive"))
      (node (ref "USB-C") (pin "B7") (pinfunction "D-2_B7") (pintype "passive"))
    )
    (net (code "44") (name "VBAT") (class "Default")
      (node (ref "BATT") (pin "2") (pinfunction "2_2") (pintype "passive"))
      (node (ref "C5") (pin "1") (pinfunction "1_1") (pintype "passive"))
      (node (ref "C7") (pin "2") (pinfunction "2_2") (pintype "passive"))
      (node (ref "IC2") (pin "3") (pinfunction "VBAT_3") (pintype "bidirectional"))
      (node (ref "L1") (pin "1") (pinfunction "1_1") (pintype "passive"))
      (node (ref "R22") (pin "1") (pinfunction "1_1") (pintype "passive"))
      (node (ref "REGULATOR") (pin "2") (pinfunction "EN_2") (pintype "input"))
      (node (ref "REGULATOR") (pin "3") (pinfunction "VBAT_3") (pintype "input"))
      (node (ref "U1") (pin "2") (pinfunction "CELL_2") (pintype "passive"))
      (node (ref "U1") (pin "3") (pinfunction "VDD_3") (pintype "power_in"))
    )
    (net (code "45") (name "VBAT_SENSE") (class "Default")
      (node (ref "J1") (pin "A3") (pinfunction "A3_A3") (pintype "passive"))
      (node (ref "R22") (pin "2") (pinfunction "2_2") (pintype "passive"))
      (node (ref "R23") (pin "1") (pinfunction "1_1") (pintype "passive"))
    )
    (net (code "46") (name "VBUS") (class "Default")
      (node (ref "C2") (pin "1") (pinfunction "1_1") (pintype "passive"))
      (node (ref "D1") (pin "2") (pinfunction "A_2") (pintype "passive"))
      (node (ref "IC2") (pin "4") (pinfunction "VDD_4") (pintype "power_in"))
      (node (ref "R27") (pin "1") (pinfunction "1_1") (pintype "passive"))
      (node (ref "USB-C") (pin "A4") (pinfunction "VBUS_A4") (pintype "passive"))
      (node (ref "USB-C") (pin "A9") (pinfunction "VBUS1_A9") (pintype "passive"))
      (node (ref "USB-C") (pin "B4") (pinfunction "VBUS2_B4") (pintype "passive"))
      (node (ref "USB-C") (pin "B9") (pinfunction "VBUS3_B9") (pintype "passive"))
    )
    (net (code "47") (name "VOLUME_DOWN") (class "Default")
      (node (ref "IC1") (pin "15") (pinfunction "P1_5_15") (pintype "bidirectional"))
      (node (ref "R25") (pin "1") (pinfunction "1_1") (pintype "passive"))
      (node (ref "S2") (pin "1") (pinfunction "1_1") (pintype "bidirectional"))
      (node (ref "S2") (pin "3") (pinfunction "1_3") (pintype "bidirectional"))
    )
    (net (code "48") (name "VOLUME_UP") (class "Default")
      (node (ref "IC1") (pin "14") (pinfunction "P1_4_14") (pintype "bidirectional"))
      (node (ref "R24") (pin "1") (pinfunction "1_1") (pintype "passive"))
      (node (ref "S1") (pin "1") (pinfunction "1_1") (pintype "bidirectional"))
      (node (ref "S1") (pin "3") (pinfunction "1_3") (pintype "bidirectional"))
    )
    (net (code "49") (name "X") (class "Default")
      (node (ref "IC1") (pin "12") (pinfunction "P0_6_12") (pintype "bidirectional"))
      (node (ref "R1") (pin "1") (pinfunction "1_1") (pintype "passive"))
      (node (ref "X") (pin "P$1") (pinfunction "1_P$1") (pintype "passive"))
      (node (ref "X") (pin "P$3") (pinfunction "1_P$3") (pintype "passive"))
    )
    (net (code "50") (name "Y") (class "Default")
      (node (ref "IC1") (pin "13") (pinfunction "P0_7_13") (pintype "bidirectional"))
      (node (ref "R2") (pin "1") (pinfunction "1_1") (pintype "passive"))
      (node (ref "Y") (pin "P$1") (pinfunction "1_P$1") (pintype "passive"))
      (node (ref "Y") (pin "P$3") (pinfunction "1_P$3") (pintype "passive"))
    )
    (net (code "51") (name "unconnected-(HAPTIC-IN{slash}TRIG-Pad4)") (class "Default")
      (node (ref "HAPTIC") (pin "4") (pinfunction "IN/TRIG_4") (pintype "bidirectional"))
    )
    (net (code "52") (name "unconnected-(HAPTIC-REG-Pad1)") (class "Default")
      (node (ref "HAPTIC") (pin "1") (pinfunction "REG_1") (pintype "bidirectional"))
    )
    (net (code "53") (name "unconnected-(IC1-P1_2-Pad3)") (class "Default")
      (node (ref "IC1") (pin "3") (pinfunction "P1_2_3") (pintype "bidirectional"))
    )
    (net (code "54") (name "unconnected-(IC1-P1_6-Pad16)") (class "Default")
      (node (ref "IC1") (pin "16") (pinfunction "P1_6_16") (pintype "bidirectional"))
    )
    (net (code "55") (name "unconnected-(IC1-P1_7-Pad17)") (class "Default")
      (node (ref "IC1") (pin "17") (pinfunction "P1_7_17") (pintype "bidirectional"))
    )
    (net (code "56") (name "unconnected-(J1-PadA13)") (class "Default")
      (node (ref "J1") (pin "A13") (pinfunction "A13_A13") (pintype "passive"))
    )
    (net (code "57") (name "unconnected-(J1-PadA15)") (class "Default")
      (node (ref "J1") (pin "A15") (pinfunction "A15_A15") (pintype "passive"))
    )
    (net (code "58") (name "unconnected-(J1-PadB13)") (class "Default")
      (node (ref "J1") (pin "B13") (pinfunction "B13_B13") (pintype "passive"))
    )
    (net (code "59") (name "unconnected-(J1-PadB15)") (class "Default")
      (node (ref "J1") (pin "B15") (pinfunction "B15_B15") (pintype "passive"))
    )
    (net (code "60") (name "unconnected-(J2-PadCD1)") (class "Default")
      (node (ref "J2") (pin "CD1") (pinfunction "CD1_CD1") (pintype "bidirectional"))
    )
    (net (code "61") (name "unconnected-(J2-PadCD2)") (class "Default")
      (node (ref "J2") (pin "CD2") (pinfunction "CD2_CD2") (pintype "bidirectional"))
    )
    (net (code "62") (name "unconnected-(J2-RSV-PadRSV1)") (class "Default")
      (node (ref "J2") (pin "RSV1") (pinfunction "RSV_RSV1") (pintype "bidirectional"))
    )
    (net (code "63") (name "unconnected-(J2-RSV-PadRSV2)") (class "Default")
      (node (ref "J2") (pin "RSV2") (pinfunction "RSV_RSV2") (pintype "bidirectional"))
    )
    (net (code "64") (name "unconnected-(USB-C-SBU1-PadA8)") (class "Default")
      (node (ref "USB-C") (pin "A8") (pinfunction "SBU1_A8") (pintype "passive"))
    )
    (net (code "65") (name "unconnected-(USB-C-SBU2-PadB8)") (class "Default")
      (node (ref "USB-C") (pin "B8") (pinfunction "SBU2_B8") (pintype "passive"))
    )
    (net (code "66") (name "~{BAT_ALERT}") (class "Default")
      (node (ref "IC1") (pin "4") (pinfunction "P1_3_4") (pintype "bidirectional"))
      (node (ref "R21") (pin "2") (pinfunction "2_2") (pintype "passive"))
      (node (ref "U1") (pin "5") (pinfunction "~{ALRT}_5") (pintype "output"))
    )
  )
)
